# MCU.net
KiCad netlist of a schematic drawn in Altium Designer
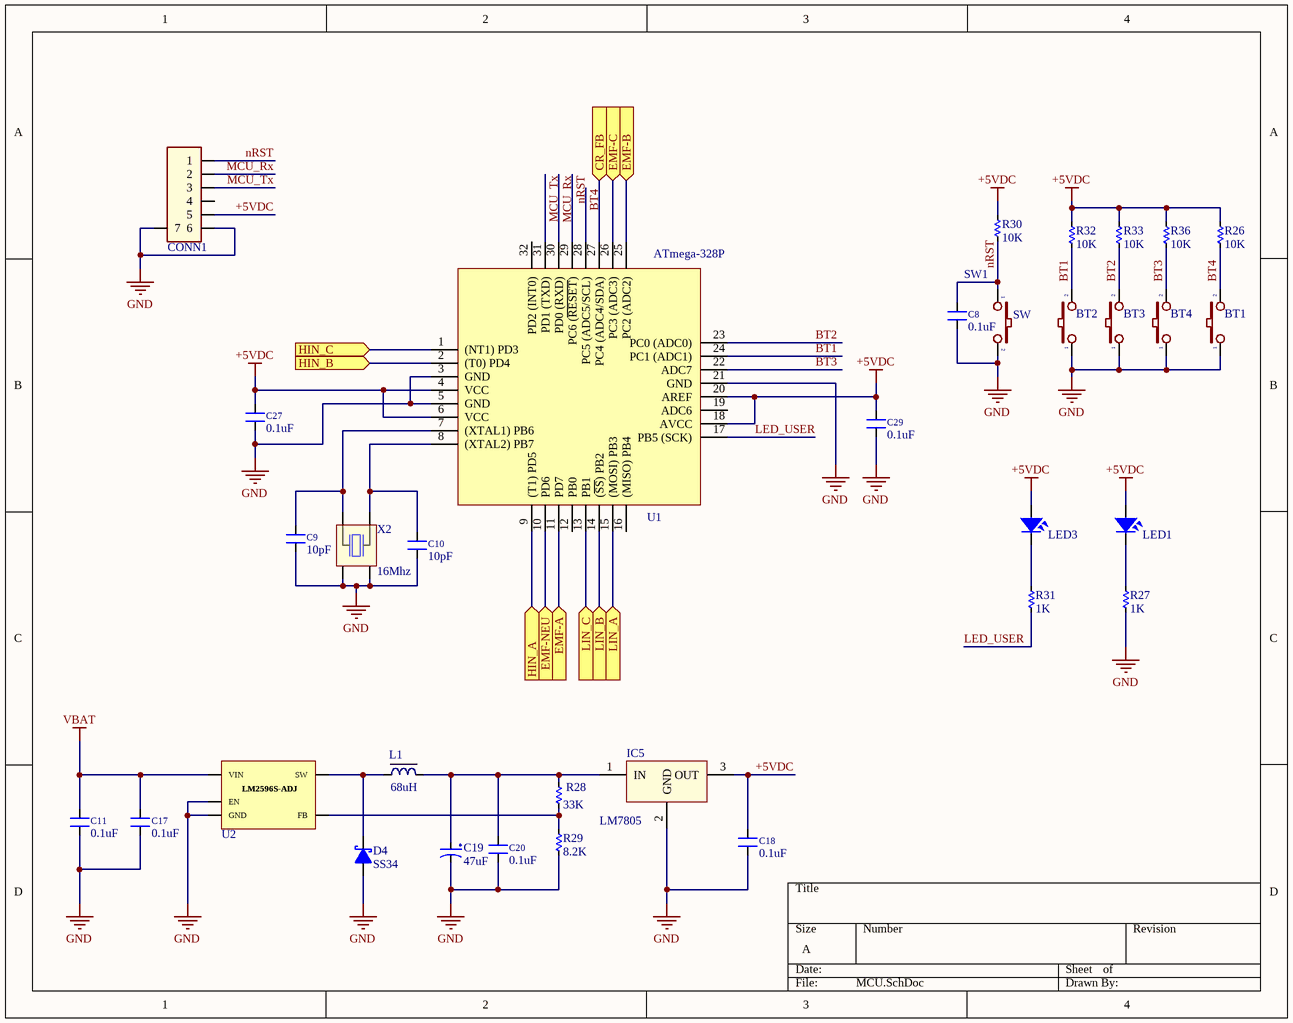
[diagram p0: MCU.SchDoc]

(export (version "E")
  (design (tool "Eeschema 10.0.6"))
  (components
    (comp (ref "BT1")
      (value "BUTTON1")
      (footprint "SW4_SMD")
      (libsource (lib "Sang_Library") (part "BUTTON1"))
    )
    (comp (ref "BT2")
      (value "BUTTON1")
      (footprint "SW4_SMD")
      (libsource (lib "Sang_Library") (part "BUTTON1"))
    )
    (comp (ref "BT3")
      (value "BUTTON1")
      (footprint "SW4_SMD")
      (libsource (lib "Sang_Library") (part "BUTTON1"))
    )
    (comp (ref "BT4")
      (value "BUTTON1")
      (footprint "SW4_SMD")
      (libsource (lib "Sang_Library") (part "BUTTON1"))
    )
    (comp (ref "C8")
      (value "0.1uF")
      (footprint "CN-SMD-0603")
      (description "CAP SMD")
      (fields (field (name "DESIGNED BY") "VanDungEvn"))
      (libsource (lib "Sang_Library") (part "CAP SMD"))
    )
    (comp (ref "C9")
      (value "10pF")
      (footprint "CN-SMD-0805")
      (description "CAP SMD")
      (fields (field (name "DESIGNED BY") "VanDungEvn"))
      (libsource (lib "Sang_Library") (part "CAP SMD"))
    )
    (comp (ref "C10")
      (value "10pF")
      (footprint "CN-SMD-0805")
      (description "CAP SMD")
      (fields (field (name "DESIGNED BY") "VanDungEvn"))
      (libsource (lib "Sang_Library") (part "CAP SMD"))
    )
    (comp (ref "C11")
      (value "0.1uF")
      (footprint "CN-SMD-1206")
      (description "CAP SMD")
      (fields (field (name "DESIGNED BY") "VanDungEvn"))
      (libsource (lib "Sang_Library") (part "CAP SMD"))
    )
    (comp (ref "C17")
      (value "0.1uF")
      (footprint "CN-SMD-0805")
      (description "CAP SMD")
      (fields (field (name "DESIGNED BY") "VanDungEvn"))
      (libsource (lib "Sang_Library") (part "CAP SMD"))
    )
    (comp (ref "C18")
      (value "0.1uF")
      (footprint "SM-CAP-0603")
      (description "CAP SMD")
      (fields (field (name "DESIGNED BY") "VanDungEvn"))
      (libsource (lib "Sang_Library") (part "CAP SMD"))
    )
    (comp (ref "C19")
      (value "47uF")
      (footprint "CAP-ALU-SMD-6.3x7.7x2.2")
      (description "CAP-ALU-SMD")
      (fields (field (name "PUBLISHER") "Altium Limited"))
      (libsource (lib "Sang_Library") (part "CAP-ALU-SMD"))
    )
    (comp (ref "C20")
      (value "0.1uF")
      (footprint "SM-CAP-0603")
      (description "CAP SMD")
      (fields (field (name "DESIGNED BY") "VanDungEvn"))
      (libsource (lib "Sang_Library") (part "CAP SMD"))
    )
    (comp (ref "C27")
      (value "0.1uF")
      (footprint "SM-CAP-0603")
      (description "CAP SMD")
      (fields (field (name "DESIGNED BY") "VanDungEvn"))
      (libsource (lib "Sang_Library") (part "CAP SMD"))
    )
    (comp (ref "C29")
      (value "0.1uF")
      (footprint "CN-SMD-0603")
      (description "CAP SMD")
      (fields (field (name "DESIGNED BY") "VanDungEvn"))
      (libsource (lib "Sang_Library") (part "CAP SMD"))
    )
    (comp (ref "CONN1")
      (value "CONNECTOR 6P")
      (footprint "JST-PH2.0_6P")
      (libsource (lib "Huan") (part "CONNECTOR 6P"))
    )
    (comp (ref "D4")
      (value "SS34")
      (footprint "DO-214AC(SMA)")
      (description "Diode  Schottky")
      (libsource (lib "Sang_Library") (part "Diode  Schottky"))
    )
    (comp (ref "IC5")
      (value "LM7805")
      (footprint "TO263-DDPAK")
      (description "On ap +, from + 5 to + 24VDC")
      (libsource (lib "Sang_Library") (part "LM78xx"))
    )
    (comp (ref "L1")
      (value "68uH")
      (footprint "L-SMD-CDRH127-M-12x7")
      (description "inductor-SMD")
      (libsource (lib "Sang_Library") (part "inductor-SMD"))
    )
    (comp (ref "LED1")
      (value "LED SMD")
      (footprint "SM-LED-0603")
      (libsource (lib "Sang_Library") (part "LED-SMD-0805"))
    )
    (comp (ref "LED3")
      (value "LED SMD")
      (footprint "SM-LED-0603")
      (libsource (lib "Sang_Library") (part "LED-SMD-0805"))
    )
    (comp (ref "R26")
      (value "10K")
      (footprint "RES-SMD-0603")
      (description "Resistor")
      (fields
        (field (name "MANUFACTURER") "Generic Components")
        (field (name "PUBLISHER") "Altium Hobart Technology Centre")
      )
      (libsource (lib "Sang_Library") (part "Res-SMD"))
    )
    (comp (ref "R27")
      (value "1K")
      (footprint "RES-SMD-0603")
      (description "Resistor")
      (fields
        (field (name "MANUFACTURER") "Generic Components")
        (field (name "PUBLISHER") "Altium Hobart Technology Centre")
      )
      (libsource (lib "Sang_Library") (part "Res-SMD"))
    )
    (comp (ref "R28")
      (value "33K")
      (footprint "RES-SMD-0805")
      (description "Resistor")
      (fields
        (field (name "MANUFACTURER") "Generic Components")
        (field (name "PUBLISHER") "Altium Hobart Technology Centre")
      )
      (libsource (lib "Sang_Library") (part "Res-SMD"))
    )
    (comp (ref "R29")
      (value "8.2K")
      (footprint "RES-SMD-0805")
      (description "Resistor")
      (fields
        (field (name "MANUFACTURER") "Generic Components")
        (field (name "PUBLISHER") "Altium Hobart Technology Centre")
      )
      (libsource (lib "Sang_Library") (part "Res-SMD"))
    )
    (comp (ref "R30")
      (value "10K")
      (footprint "RES-SMD-0603")
      (description "Resistor")
      (fields
        (field (name "MANUFACTURER") "Generic Components")
        (field (name "PUBLISHER") "Altium Hobart Technology Centre")
      )
      (libsource (lib "Sang_Library") (part "Res-SMD"))
    )
    (comp (ref "R31")
      (value "1K")
      (footprint "RES-SMD-0603")
      (description "Resistor")
      (fields
        (field (name "MANUFACTURER") "Generic Components")
        (field (name "PUBLISHER") "Altium Hobart Technology Centre")
      )
      (libsource (lib "Sang_Library") (part "Res-SMD"))
    )
    (comp (ref "R32")
      (value "10K")
      (footprint "RES-SMD-0603")
      (description "Resistor")
      (fields
        (field (name "MANUFACTURER") "Generic Components")
        (field (name "PUBLISHER") "Altium Hobart Technology Centre")
      )
      (libsource (lib "Sang_Library") (part "Res-SMD"))
    )
    (comp (ref "R33")
      (value "10K")
      (footprint "RES-SMD-0603")
      (description "Resistor")
      (fields
        (field (name "MANUFACTURER") "Generic Components")
        (field (name "PUBLISHER") "Altium Hobart Technology Centre")
      )
      (libsource (lib "Sang_Library") (part "Res-SMD"))
    )
    (comp (ref "R36")
      (value "10K")
      (footprint "RES-SMD-0603")
      (description "Resistor")
      (fields
        (field (name "MANUFACTURER") "Generic Components")
        (field (name "PUBLISHER") "Altium Hobart Technology Centre")
      )
      (libsource (lib "Sang_Library") (part "Res-SMD"))
    )
    (comp (ref "SW1")
      (value "SW")
      (footprint "SW-SMD - 3x4")
      (description "Switch button 2 pin")
      (libsource (lib "Sang_Library") (part "SW2"))
    )
    (comp (ref "U1")
      (value "ATmega-328P")
      (footprint "TQFP32")
      (description "Atmega328psmd")
      (libsource (lib "Sang_Library") (part "Atmega328P-SMD"))
    )
    (comp (ref "U2") (value "LM2596S") (footprint "TO-263_5P") (libsource (lib "Huan") (part "LM2596S")))
    (comp (ref "X2")
      (value "16Mhz")
      (footprint "XT4 SMD 3225")
      (description "XTAL SMD 3225, 12MHz, Cl=18pF, Tol: ±30ppm, Stab: ±30ppm")
      (libsource (lib "Sang_Library") (part "XTAL SMD 4PIN"))
    )
  )
  (nets
    (net (code "1") (name "+5VDC") (class "Default")
      (node (ref "C18") (pin "2") (pinfunction "2_2") (pintype "passive"))
      (node (ref "C27") (pin "2") (pinfunction "2_2") (pintype "passive"))
      (node (ref "C29") (pin "2") (pinfunction "2_2") (pintype "passive"))
      (node (ref "CONN1") (pin "5") (pinfunction "5_5") (pintype "passive"))
      (node (ref "IC5") (pin "3") (pinfunction "OUT_3") (pintype "passive"))
      (node (ref "LED1") (pin "1") (pinfunction "1_1") (pintype "passive"))
      (node (ref "LED3") (pin "1") (pinfunction "1_1") (pintype "passive"))
      (node (ref "R26") (pin "2") (pinfunction "2_2") (pintype "passive"))
      (node (ref "R30") (pin "2") (pinfunction "2_2") (pintype "passive"))
      (node (ref "R32") (pin "2") (pinfunction "2_2") (pintype "passive"))
      (node (ref "R33") (pin "2") (pinfunction "2_2") (pintype "passive"))
      (node (ref "R36") (pin "2") (pinfunction "2_2") (pintype "passive"))
      (node (ref "U1") (pin "18") (pinfunction "AVCC_18") (pintype "passive"))
      (node (ref "U1") (pin "20") (pinfunction "AREF_20") (pintype "passive"))
      (node (ref "U1") (pin "4") (pinfunction "VCC_4") (pintype "passive"))
      (node (ref "U1") (pin "6") (pinfunction "VCC_6") (pintype "passive"))
    )
    (net (code "2") (name "/BT1") (class "Default")
      (node (ref "BT2") (pin "2") (pinfunction "2_2") (pintype "passive"))
      (node (ref "R32") (pin "1") (pinfunction "1_1") (pintype "passive"))
      (node (ref "U1") (pin "24") (pinfunction "PC1_(ADC1)_24") (pintype "passive"))
    )
    (net (code "3") (name "/BT2") (class "Default")
      (node (ref "BT3") (pin "2") (pinfunction "2_2") (pintype "passive"))
      (node (ref "R33") (pin "1") (pinfunction "1_1") (pintype "passive"))
      (node (ref "U1") (pin "23") (pinfunction "PC0_(ADC0)_23") (pintype "passive"))
    )
    (net (code "4") (name "/BT3") (class "Default")
      (node (ref "BT4") (pin "2") (pinfunction "2_2") (pintype "passive"))
      (node (ref "R36") (pin "1") (pinfunction "1_1") (pintype "passive"))
      (node (ref "U1") (pin "22") (pinfunction "ADC7_22") (pintype "passive"))
    )
    (net (code "5") (name "/BT4") (class "Default")
      (node (ref "BT1") (pin "2") (pinfunction "2_2") (pintype "passive"))
      (node (ref "R26") (pin "1") (pinfunction "1_1") (pintype "passive"))
      (node (ref "U1") (pin "28") (pinfunction "PC5_(ADC5/SCL)_28") (pintype "passive"))
    )
    (net (code "6") (name "/CR_FB") (class "Default")
      (node (ref "U1") (pin "27") (pinfunction "PC4_(ADC4/SDA)_27") (pintype "passive"))
    )
    (net (code "7") (name "/EMF-A") (class "Default")
      (node (ref "U1") (pin "11") (pinfunction "PD7_11") (pintype "passive"))
    )
    (net (code "8") (name "/EMF-B") (class "Default")
      (node (ref "U1") (pin "25") (pinfunction "PC2_(ADC2)_25") (pintype "passive"))
    )
    (net (code "9") (name "/EMF-C") (class "Default")
      (node (ref "U1") (pin "26") (pinfunction "PC3_(ADC3)_26") (pintype "passive"))
    )
    (net (code "10") (name "/EMF-NEU") (class "Default")
      (node (ref "U1") (pin "10") (pinfunction "PD6_10") (pintype "passive"))
    )
    (net (code "11") (name "/HIN_A") (class "Default")
      (node (ref "U1") (pin "9") (pinfunction "(T1)_PD5_9") (pintype "passive"))
    )
    (net (code "12") (name "/HIN_B") (class "Default")
      (node (ref "U1") (pin "2") (pinfunction "(T0)_PD4_2") (pintype "passive"))
    )
    (net (code "13") (name "/HIN_C") (class "Default")
      (node (ref "U1") (pin "1") (pinfunction "(NT1)_PD3_1") (pintype "passive"))
    )
    (net (code "14") (name "/LED_USER") (class "Default")
      (node (ref "R31") (pin "2") (pinfunction "2_2") (pintype "passive"))
      (node (ref "U1") (pin "17") (pinfunction "PB5_(SCK)_17") (pintype "passive"))
    )
    (net (code "15") (name "/LIN_A") (class "Default")
      (node (ref "U1") (pin "15") (pinfunction "(MOSI)_PB3_15") (pintype "passive"))
    )
    (net (code "16") (name "/LIN_B") (class "Default")
      (node (ref "U1") (pin "14") (pinfunction "(~{SS})_PB2_14") (pintype "passive"))
    )
    (net (code "17") (name "/LIN_C") (class "Default")
      (node (ref "U1") (pin "13") (pinfunction "PB1_13") (pintype "passive"))
    )
    (net (code "18") (name "/MCU_Rx") (class "Default")
      (node (ref "CONN1") (pin "2") (pinfunction "2_2") (pintype "passive"))
      (node (ref "U1") (pin "30") (pinfunction "PD0_(RXD)_30") (pintype "passive"))
    )
    (net (code "19") (name "/MCU_Tx") (class "Default")
      (node (ref "CONN1") (pin "3") (pinfunction "3_3") (pintype "passive"))
      (node (ref "U1") (pin "31") (pinfunction "PD1_(TXD)_31") (pintype "passive"))
    )
    (net (code "20") (name "/nRST") (class "Default")
      (node (ref "C8") (pin "1") (pinfunction "1_1") (pintype "passive"))
      (node (ref "CONN1") (pin "1") (pinfunction "1_1") (pintype "passive"))
      (node (ref "R30") (pin "1") (pinfunction "1_1") (pintype "passive"))
      (node (ref "SW1") (pin "1") (pinfunction "1_1") (pintype "passive"))
      (node (ref "U1") (pin "29") (pinfunction "PC6_(~{RESET})_29") (pintype "passive"))
    )
    (net (code "21") (name "GND") (class "Default")
      (node (ref "BT1") (pin "1") (pinfunction "1_1") (pintype "passive"))
      (node (ref "BT2") (pin "1") (pinfunction "1_1") (pintype "passive"))
      (node (ref "BT3") (pin "1") (pinfunction "1_1") (pintype "passive"))
      (node (ref "BT4") (pin "1") (pinfunction "1_1") (pintype "passive"))
      (node (ref "C10") (pin "1") (pinfunction "1_1") (pintype "passive"))
      (node (ref "C11") (pin "1") (pinfunction "1_1") (pintype "passive"))
      (node (ref "C17") (pin "1") (pinfunction "1_1") (pintype "passive"))
      (node (ref "C18") (pin "1") (pinfunction "1_1") (pintype "passive"))
      (node (ref "C19") (pin "2") (pinfunction "2_2") (pintype "passive"))
      (node (ref "C20") (pin "1") (pinfunction "1_1") (pintype "passive"))
      (node (ref "C27") (pin "1") (pinfunction "1_1") (pintype "passive"))
      (node (ref "C29") (pin "1") (pinfunction "1_1") (pintype "passive"))
      (node (ref "C8") (pin "2") (pinfunction "2_2") (pintype "passive"))
      (node (ref "C9") (pin "1") (pinfunction "1_1") (pintype "passive"))
      (node (ref "CONN1") (pin "6") (pinfunction "6_6") (pintype "passive"))
      (node (ref "CONN1") (pin "7") (pinfunction "7_7") (pintype "passive"))
      (node (ref "D4") (pin "A") (pinfunction "A_A") (pintype "passive"))
      (node (ref "IC5") (pin "2") (pinfunction "GND_2") (pintype "passive"))
      (node (ref "R27") (pin "2") (pinfunction "2_2") (pintype "passive"))
      (node (ref "R29") (pin "2") (pinfunction "2_2") (pintype "passive"))
      (node (ref "SW1") (pin "2") (pinfunction "2_2") (pintype "passive"))
      (node (ref "U1") (pin "21") (pinfunction "GND_21") (pintype "passive"))
      (node (ref "U1") (pin "3") (pinfunction "GND_3") (pintype "passive"))
      (node (ref "U1") (pin "5") (pinfunction "GND_5") (pintype "passive"))
      (node (ref "U2") (pin "3") (pinfunction "GND_3") (pintype "passive"))
      (node (ref "U2") (pin "5") (pinfunction "EN_5") (pintype "passive"))
      (node (ref "X2") (pin "2") (pinfunction "inp_2") (pintype "passive"))
      (node (ref "X2") (pin "4") (pinfunction "inp_4") (pintype "passive"))
    )
    (net (code "22") (name "Net-(IC5-IN)") (class "Default")
      (node (ref "C19") (pin "1") (pinfunction "1_1") (pintype "passive"))
      (node (ref "C20") (pin "2") (pinfunction "2_2") (pintype "passive"))
      (node (ref "IC5") (pin "1") (pinfunction "IN_1") (pintype "passive"))
      (node (ref "L1") (pin "2") (pinfunction "2_2") (pintype "passive"))
      (node (ref "R28") (pin "2") (pinfunction "2_2") (pintype "passive"))
    )
    (net (code "23") (name "Net-(LED1-Pad2)") (class "Default")
      (node (ref "LED1") (pin "2") (pinfunction "2_2") (pintype "passive"))
      (node (ref "R27") (pin "1") (pinfunction "1_1") (pintype "passive"))
    )
    (net (code "24") (name "Net-(LED3-Pad2)") (class "Default")
      (node (ref "LED3") (pin "2") (pinfunction "2_2") (pintype "passive"))
      (node (ref "R31") (pin "1") (pinfunction "1_1") (pintype "passive"))
    )
    (net (code "25") (name "Net-(U1-(XTAL1)_PB6)") (class "Default")
      (node (ref "C9") (pin "2") (pinfunction "2_2") (pintype "passive"))
      (node (ref "U1") (pin "7") (pinfunction "(XTAL1)_PB6_7") (pintype "passive"))
      (node (ref "X2") (pin "3") (pinfunction "out_3") (pintype "passive"))
    )
    (net (code "26") (name "Net-(U1-(XTAL2)_PB7)") (class "Default")
      (node (ref "C10") (pin "2") (pinfunction "2_2") (pintype "passive"))
      (node (ref "U1") (pin "8") (pinfunction "(XTAL2)_PB7_8") (pintype "passive"))
      (node (ref "X2") (pin "1") (pinfunction "inp_1") (pintype "passive"))
    )
    (net (code "27") (name "Net-(U2-FB)") (class "Default")
      (node (ref "R28") (pin "1") (pinfunction "1_1") (pintype "passive"))
      (node (ref "R29") (pin "1") (pinfunction "1_1") (pintype "passive"))
      (node (ref "U2") (pin "4") (pinfunction "FB_4") (pintype "passive"))
    )
    (net (code "28") (name "Net-(U2-SW)") (class "Default")
      (node (ref "D4") (pin "K") (pinfunction "K_K") (pintype "passive"))
      (node (ref "L1") (pin "1") (pinfunction "1_1") (pintype "passive"))
      (node (ref "U2") (pin "2") (pinfunction "SW_2") (pintype "passive"))
    )
    (net (code "29") (name "VBAT") (class "Default")
      (node (ref "C11") (pin "2") (pinfunction "2_2") (pintype "passive"))
      (node (ref "C17") (pin "2") (pinfunction "2_2") (pintype "passive"))
      (node (ref "U2") (pin "1") (pinfunction "VIN_1") (pintype "passive"))
    )
    (net (code "30") (name "unconnected-(CONN1-Pad4)") (class "Default")
      (node (ref "CONN1") (pin "4") (pinfunction "4_4") (pintype "passive"))
    )
    (net (code "31") (name "unconnected-(U1-(MISO)_PB4-Pad16)") (class "Default")
      (node (ref "U1") (pin "16") (pinfunction "(MISO)_PB4_16") (pintype "passive"))
    )
    (net (code "32") (name "unconnected-(U1-ADC6-Pad19)") (class "Default")
      (node (ref "U1") (pin "19") (pinfunction "ADC6_19") (pintype "passive"))
    )
    (net (code "33") (name "unconnected-(U1-PB0-Pad12)") (class "Default")
      (node (ref "U1") (pin "12") (pinfunction "PB0_12") (pintype "passive"))
    )
    (net (code "34") (name "unconnected-(U1-PD2_(INT0)-Pad32)") (class "Default")
      (node (ref "U1") (pin "32") (pinfunction "PD2_(INT0)_32") (pintype "passive"))
    )
  )
)
